# 156-01A_LCNC_Combo_board.net
KiCad netlist of a schematic drawn in EAGLE
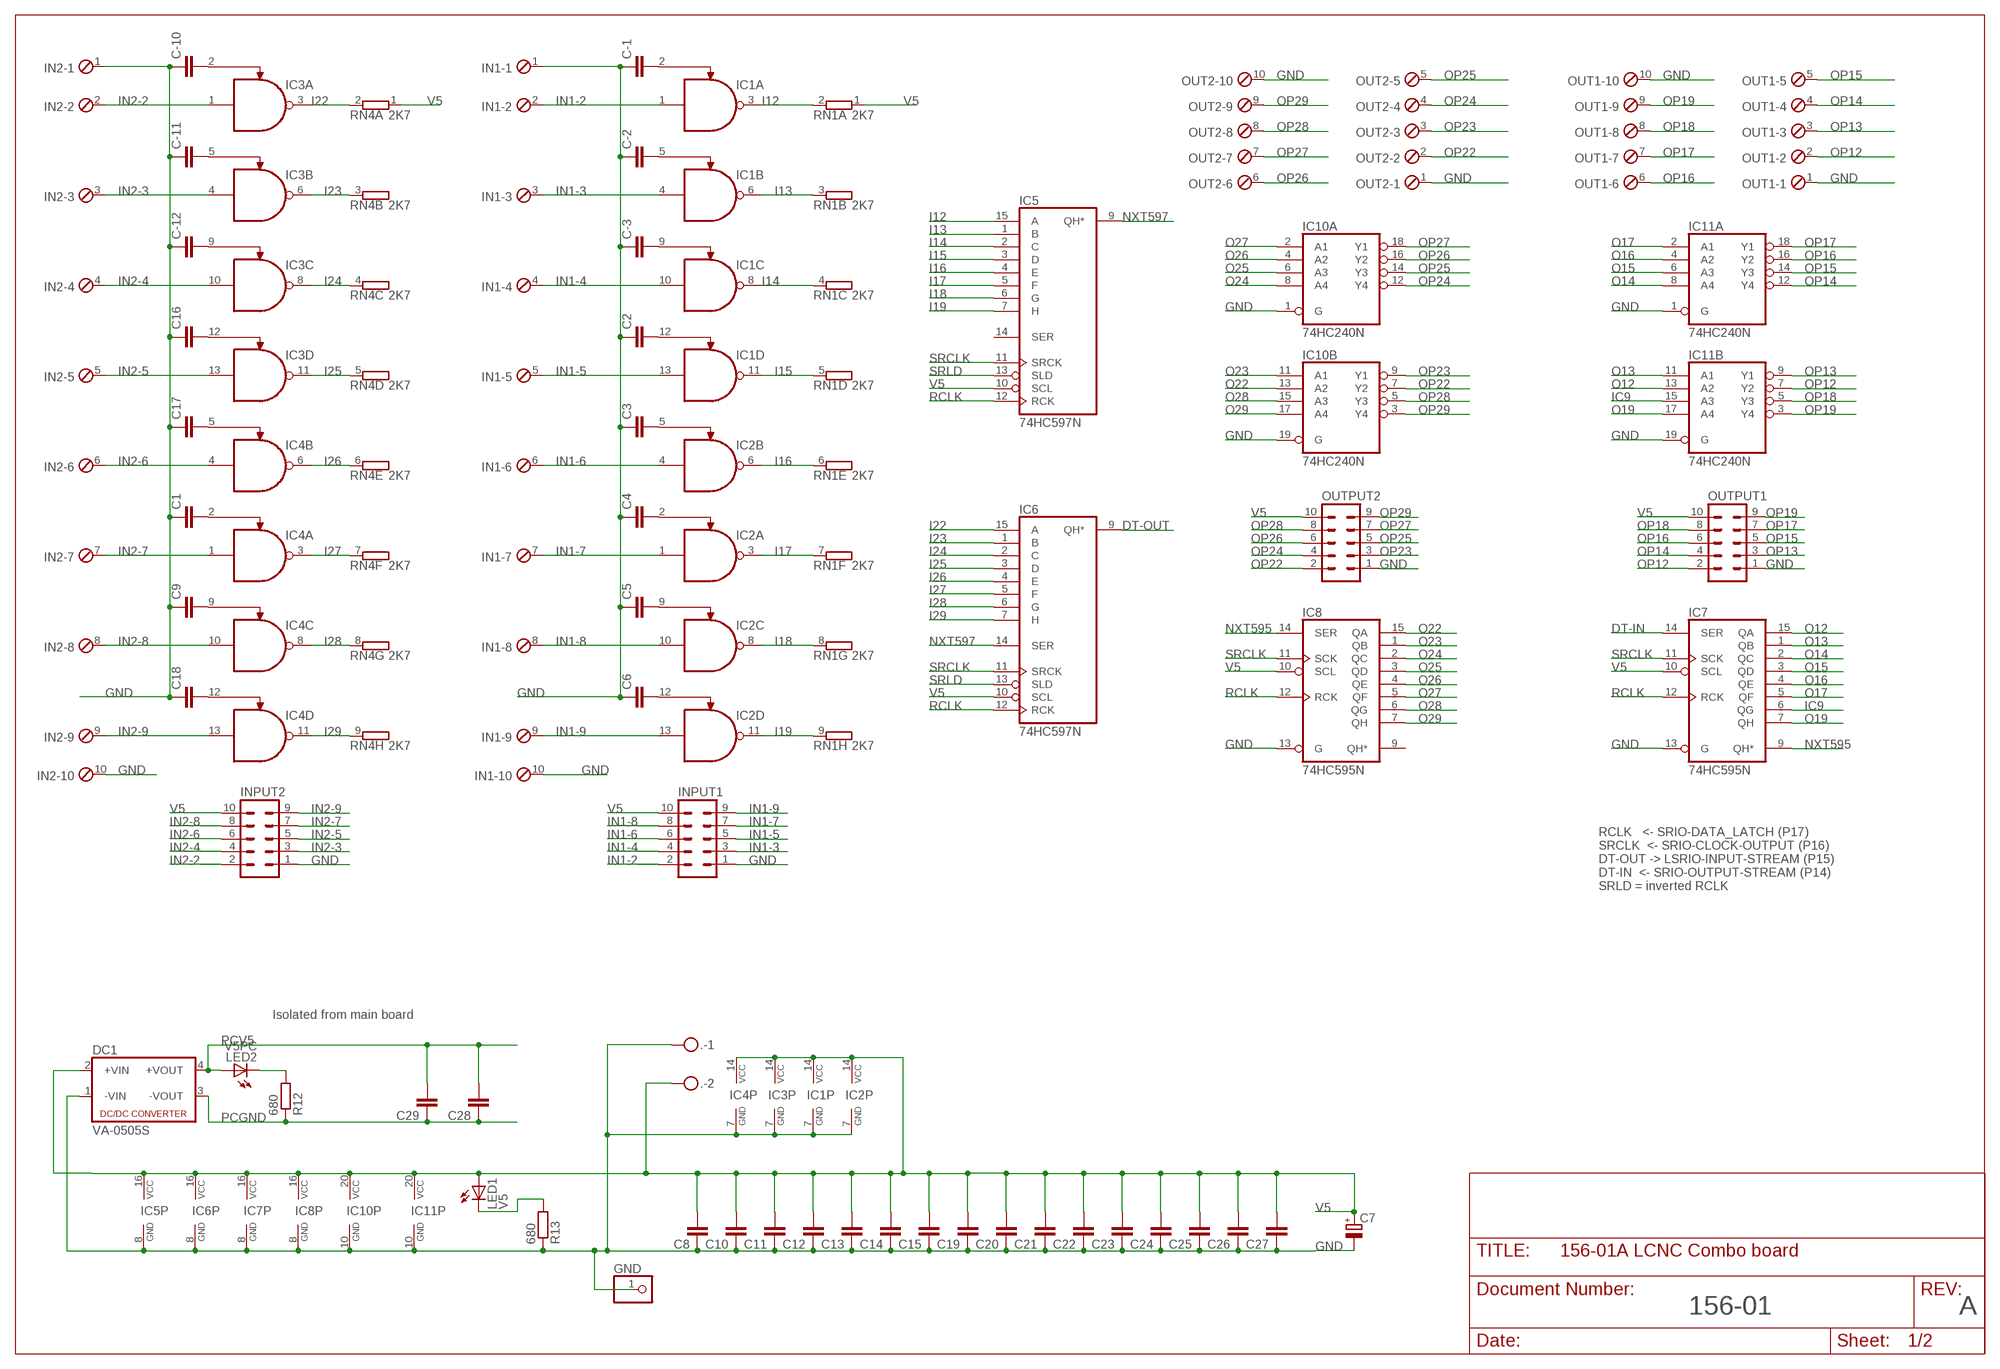
[diagram p0: schematic, sheet 1]
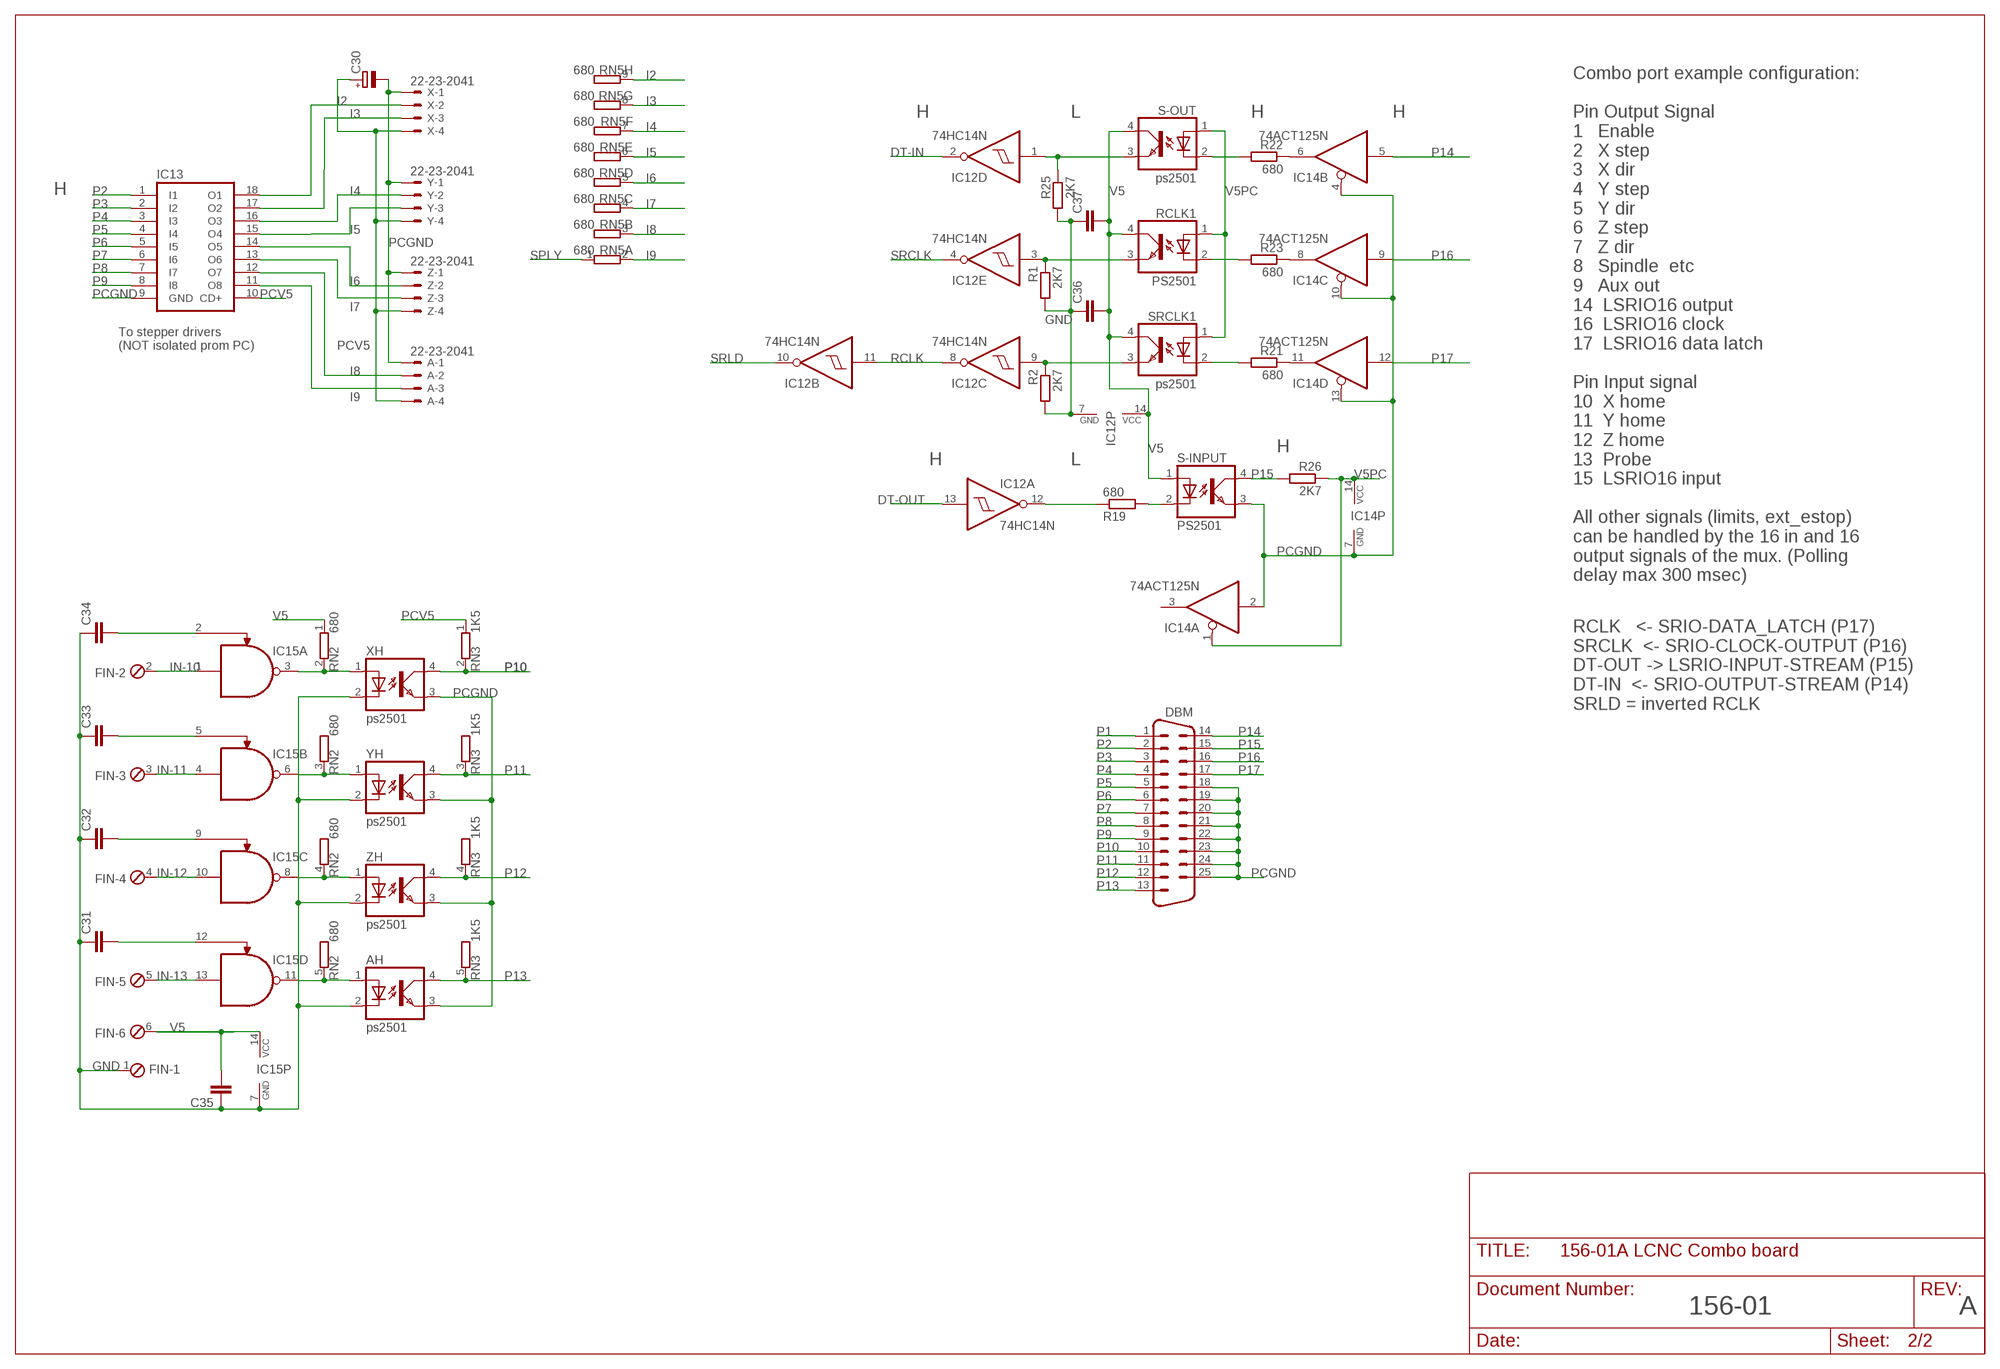
[diagram p1: schematic, sheet 2]

(export (version "E")
  (design (tool "Eeschema 10.0.6"))
  (components
    (comp (ref ".")
      (value "MKDSN1,5/2-5,08")
      (footprint "eagle-import:MKDSN1,5_2-5,08")
      (libsource (lib "eagle-import") (part "MKDSN1,5/2-5,08"))
    )
    (comp (ref "C-1")
      (value "C-EU025-024X044")
      (footprint "eagle-import:C025-024X044")
      (libsource (lib "eagle-import") (part "C-EU025-024X044"))
    )
    (comp (ref "C-2")
      (value "C-EU025-024X044")
      (footprint "eagle-import:C025-024X044")
      (libsource (lib "eagle-import") (part "C-EU025-024X044"))
    )
    (comp (ref "C-3")
      (value "C-EU025-024X044")
      (footprint "eagle-import:C025-024X044")
      (libsource (lib "eagle-import") (part "C-EU025-024X044"))
    )
    (comp (ref "C-10")
      (value "C-EU025-024X044")
      (footprint "eagle-import:C025-024X044")
      (libsource (lib "eagle-import") (part "C-EU025-024X044"))
    )
    (comp (ref "C-11")
      (value "C-EU025-024X044")
      (footprint "eagle-import:C025-024X044")
      (libsource (lib "eagle-import") (part "C-EU025-024X044"))
    )
    (comp (ref "C-12")
      (value "C-EU025-024X044")
      (footprint "eagle-import:C025-024X044")
      (libsource (lib "eagle-import") (part "C-EU025-024X044"))
    )
    (comp (ref "C1")
      (value "C-EU025-024X044")
      (footprint "eagle-import:C025-024X044")
      (libsource (lib "eagle-import") (part "C-EU025-024X044"))
    )
    (comp (ref "C2")
      (value "C-EU025-024X044")
      (footprint "eagle-import:C025-024X044")
      (libsource (lib "eagle-import") (part "C-EU025-024X044"))
    )
    (comp (ref "C3")
      (value "C-EU025-024X044")
      (footprint "eagle-import:C025-024X044")
      (libsource (lib "eagle-import") (part "C-EU025-024X044"))
    )
    (comp (ref "C4")
      (value "C-EU025-024X044")
      (footprint "eagle-import:C025-024X044")
      (libsource (lib "eagle-import") (part "C-EU025-024X044"))
    )
    (comp (ref "C5")
      (value "C-EU025-024X044")
      (footprint "eagle-import:C025-024X044")
      (libsource (lib "eagle-import") (part "C-EU025-024X044"))
    )
    (comp (ref "C6")
      (value "C-EU025-024X044")
      (footprint "eagle-import:C025-024X044")
      (libsource (lib "eagle-import") (part "C-EU025-024X044"))
    )
    (comp (ref "C7")
      (value "CPOL-EUE3.5-8")
      (footprint "eagle-import:E3,5-8")
      (libsource (lib "eagle-import") (part "CPOL-EUE3.5-8"))
    )
    (comp (ref "C8")
      (value "C-EU025-024X044")
      (footprint "eagle-import:C025-024X044")
      (libsource (lib "eagle-import") (part "C-EU025-024X044"))
    )
    (comp (ref "C9")
      (value "C-EU025-024X044")
      (footprint "eagle-import:C025-024X044")
      (libsource (lib "eagle-import") (part "C-EU025-024X044"))
    )
    (comp (ref "C10")
      (value "C-EU025-024X044")
      (footprint "eagle-import:C025-024X044")
      (libsource (lib "eagle-import") (part "C-EU025-024X044"))
    )
    (comp (ref "C11")
      (value "C-EU025-024X044")
      (footprint "eagle-import:C025-024X044")
      (libsource (lib "eagle-import") (part "C-EU025-024X044"))
    )
    (comp (ref "C12")
      (value "C-EU025-024X044")
      (footprint "eagle-import:C025-024X044")
      (libsource (lib "eagle-import") (part "C-EU025-024X044"))
    )
    (comp (ref "C13")
      (value "C-EU025-024X044")
      (footprint "eagle-import:C025-024X044")
      (libsource (lib "eagle-import") (part "C-EU025-024X044"))
    )
    (comp (ref "C14")
      (value "C-EU025-024X044")
      (footprint "eagle-import:C025-024X044")
      (libsource (lib "eagle-import") (part "C-EU025-024X044"))
    )
    (comp (ref "C15")
      (value "C-EU025-024X044")
      (footprint "eagle-import:C025-024X044")
      (libsource (lib "eagle-import") (part "C-EU025-024X044"))
    )
    (comp (ref "C16")
      (value "C-EU025-024X044")
      (footprint "eagle-import:C025-024X044")
      (libsource (lib "eagle-import") (part "C-EU025-024X044"))
    )
    (comp (ref "C17")
      (value "C-EU025-024X044")
      (footprint "eagle-import:C025-024X044")
      (libsource (lib "eagle-import") (part "C-EU025-024X044"))
    )
    (comp (ref "C18")
      (value "C-EU025-024X044")
      (footprint "eagle-import:C025-024X044")
      (libsource (lib "eagle-import") (part "C-EU025-024X044"))
    )
    (comp (ref "C19")
      (value "C-EU025-024X044")
      (footprint "eagle-import:C025-024X044")
      (libsource (lib "eagle-import") (part "C-EU025-024X044"))
    )
    (comp (ref "C20")
      (value "C-EU025-024X044")
      (footprint "eagle-import:C025-024X044")
      (libsource (lib "eagle-import") (part "C-EU025-024X044"))
    )
    (comp (ref "C21")
      (value "C-EU025-024X044")
      (footprint "eagle-import:C025-024X044")
      (libsource (lib "eagle-import") (part "C-EU025-024X044"))
    )
    (comp (ref "C22")
      (value "C-EU025-024X044")
      (footprint "eagle-import:C025-024X044")
      (libsource (lib "eagle-import") (part "C-EU025-024X044"))
    )
    (comp (ref "C23")
      (value "C-EU025-024X044")
      (footprint "eagle-import:C025-024X044")
      (libsource (lib "eagle-import") (part "C-EU025-024X044"))
    )
    (comp (ref "C24")
      (value "C-EU025-024X044")
      (footprint "eagle-import:C025-024X044")
      (libsource (lib "eagle-import") (part "C-EU025-024X044"))
    )
    (comp (ref "C25")
      (value "C-EU025-024X044")
      (footprint "eagle-import:C025-024X044")
      (libsource (lib "eagle-import") (part "C-EU025-024X044"))
    )
    (comp (ref "C26")
      (value "C-EU025-024X044")
      (footprint "eagle-import:C025-024X044")
      (libsource (lib "eagle-import") (part "C-EU025-024X044"))
    )
    (comp (ref "C27")
      (value "C-EU025-024X044")
      (footprint "eagle-import:C025-024X044")
      (libsource (lib "eagle-import") (part "C-EU025-024X044"))
    )
    (comp (ref "C28")
      (value "C-EU025-024X044")
      (footprint "eagle-import:C025-024X044")
      (libsource (lib "eagle-import") (part "C-EU025-024X044"))
    )
    (comp (ref "C29")
      (value "C-EU025-024X044")
      (footprint "eagle-import:C025-024X044")
      (libsource (lib "eagle-import") (part "C-EU025-024X044"))
    )
    (comp (ref "DC1")
      (value "VA-0505S")
      (footprint "eagle-import:4SIL")
      (libsource (lib "eagle-import") (part "VA-?S0505"))
    )
    (comp (ref "GND")
      (value "PINHD-1X1")
      (footprint "eagle-import:1X01")
      (libsource (lib "eagle-import") (part "PINHD-1X1"))
    )
    (comp (ref "IC1")
      (value "MC1489DIP")
      (footprint "eagle-import:DIL14")
      (libsource (lib "eagle-import") (part "MC1489DIP"))
    )
    (comp (ref "IC2")
      (value "MC1489DIP")
      (footprint "eagle-import:DIL14")
      (libsource (lib "eagle-import") (part "MC1489DIP"))
    )
    (comp (ref "IC3")
      (value "MC1489DIP")
      (footprint "eagle-import:DIL14")
      (libsource (lib "eagle-import") (part "MC1489DIP"))
    )
    (comp (ref "IC4")
      (value "MC1489DIP")
      (footprint "eagle-import:DIL14")
      (libsource (lib "eagle-import") (part "MC1489DIP"))
    )
    (comp (ref "IC5")
      (value "74HC597N")
      (footprint "eagle-import:DIL16")
      (libsource (lib "eagle-import") (part "74597NHC"))
    )
    (comp (ref "IC6")
      (value "74HC597N")
      (footprint "eagle-import:DIL16")
      (libsource (lib "eagle-import") (part "74597NHC"))
    )
    (comp (ref "IC7")
      (value "74HC595N")
      (footprint "eagle-import:DIL16")
      (libsource (lib "eagle-import") (part "74595NHC"))
    )
    (comp (ref "IC8")
      (value "74HC595N")
      (footprint "eagle-import:DIL16")
      (libsource (lib "eagle-import") (part "74595NHC"))
    )
    (comp (ref "IC10")
      (value "74HC240N")
      (footprint "eagle-import:DIL20")
      (libsource (lib "eagle-import") (part "74240NHC"))
    )
    (comp (ref "IC11")
      (value "74HC240N")
      (footprint "eagle-import:DIL20")
      (libsource (lib "eagle-import") (part "74240NHC"))
    )
    (comp (ref "IN1")
      (value "MPT10")
      (footprint "eagle-import:10POL254")
      (libsource (lib "eagle-import") (part "MPT10"))
    )
    (comp (ref "IN2")
      (value "MPT10")
      (footprint "eagle-import:10POL254")
      (libsource (lib "eagle-import") (part "MPT10"))
    )
    (comp (ref "INPUT1")
      (value "ML10")
      (footprint "eagle-import:ML10")
      (libsource (lib "eagle-import") (part "ML10"))
    )
    (comp (ref "INPUT2")
      (value "ML10")
      (footprint "eagle-import:ML10")
      (libsource (lib "eagle-import") (part "ML10"))
    )
    (comp (ref "LED1")
      (value "V5")
      (footprint "eagle-import:LED3MM")
      (libsource (lib "eagle-import") (part "LED3MM"))
    )
    (comp (ref "LED2")
      (value "V5PC")
      (footprint "eagle-import:LED3MM")
      (libsource (lib "eagle-import") (part "LED3MM"))
    )
    (comp (ref "OUT1")
      (value "MPT10")
      (footprint "eagle-import:10POL254")
      (libsource (lib "eagle-import") (part "MPT10"))
    )
    (comp (ref "OUT2")
      (value "MPT10")
      (footprint "eagle-import:10POL254")
      (libsource (lib "eagle-import") (part "MPT10"))
    )
    (comp (ref "OUTPUT1")
      (value "ML10")
      (footprint "eagle-import:ML10")
      (libsource (lib "eagle-import") (part "ML10"))
    )
    (comp (ref "OUTPUT2")
      (value "ML10")
      (footprint "eagle-import:ML10")
      (libsource (lib "eagle-import") (part "ML10"))
    )
    (comp (ref "R12")
      (value "680")
      (footprint "eagle-import:0207_10")
      (libsource (lib "eagle-import") (part "R-EU_0207/10"))
    )
    (comp (ref "R13")
      (value "680")
      (footprint "eagle-import:0207_10")
      (libsource (lib "eagle-import") (part "R-EU_0207/10"))
    )
    (comp (ref "RN1")
      (value "2K7")
      (footprint "eagle-import:SIL9")
      (libsource (lib "eagle-import") (part "GE08R"))
    )
    (comp (ref "RN4")
      (value "2K7")
      (footprint "eagle-import:SIL9")
      (libsource (lib "eagle-import") (part "GE08R"))
    )
    (comp (ref "A")
      (value "22-23-2041")
      (footprint "eagle-import:22-23-2041")
      (fields (field (name "MF") "MOLEX"))
      (libsource (lib "eagle-import") (part "22-23-2041"))
    )
    (comp (ref "AH")
      (value "ps2501")
      (footprint "eagle-import:DIL04")
      (fields (field (name "MPN") "PC817X4J000F"))
      (libsource (lib "eagle-import") (part "PC817"))
    )
    (comp (ref "C30")
      (value "CPOL-EUE2.5-6")
      (footprint "eagle-import:E2,5-6")
      (libsource (lib "eagle-import") (part "CPOL-EUE2.5-6"))
    )
    (comp (ref "C31")
      (value "C-EU025-024X044")
      (footprint "eagle-import:C025-024X044")
      (libsource (lib "eagle-import") (part "C-EU025-024X044"))
    )
    (comp (ref "C32")
      (value "C-EU025-024X044")
      (footprint "eagle-import:C025-024X044")
      (libsource (lib "eagle-import") (part "C-EU025-024X044"))
    )
    (comp (ref "C33")
      (value "C-EU025-024X044")
      (footprint "eagle-import:C025-024X044")
      (libsource (lib "eagle-import") (part "C-EU025-024X044"))
    )
    (comp (ref "C34")
      (value "C-EU025-024X044")
      (footprint "eagle-import:C025-024X044")
      (libsource (lib "eagle-import") (part "C-EU025-024X044"))
    )
    (comp (ref "C35")
      (value "C-EU025-024X044")
      (footprint "eagle-import:C025-024X044")
      (libsource (lib "eagle-import") (part "C-EU025-024X044"))
    )
    (comp (ref "C36")
      (value "C-EU025-024X044")
      (footprint "eagle-import:C025-024X044")
      (libsource (lib "eagle-import") (part "C-EU025-024X044"))
    )
    (comp (ref "C37")
      (value "C-EU025-024X044")
      (footprint "eagle-import:C025-024X044")
      (libsource (lib "eagle-import") (part "C-EU025-024X044"))
    )
    (comp (ref "DBM")
      (value "M25HP")
      (footprint "eagle-import:M25HP")
      (libsource (lib "eagle-import") (part "M25HP"))
    )
    (comp (ref "FIN")
      (value "MPT6")
      (footprint "eagle-import:6POL254")
      (libsource (lib "eagle-import") (part "MPT6"))
    )
    (comp (ref "IC12")
      (value "74HC14N")
      (footprint "eagle-import:DIL14")
      (libsource (lib "eagle-import") (part "7414NHC"))
    )
    (comp (ref "IC13")
      (value "ULN2803A")
      (footprint "eagle-import:DIL18")
      (libsource (lib "eagle-import") (part "ULN2803A"))
    )
    (comp (ref "IC14")
      (value "74ACT125N")
      (footprint "eagle-import:DIL14")
      (libsource (lib "eagle-import") (part "74125NACT"))
    )
    (comp (ref "IC15")
      (value "MC1489DIP")
      (footprint "eagle-import:DIL14")
      (libsource (lib "eagle-import") (part "my-components_MC1489DIP"))
    )
    (comp (ref "R1")
      (value "2K7")
      (footprint "eagle-import:0207_10")
      (libsource (lib "eagle-import") (part "R-EU_0207/10"))
    )
    (comp (ref "R2")
      (value "2K7")
      (footprint "eagle-import:0207_10")
      (libsource (lib "eagle-import") (part "R-EU_0207/10"))
    )
    (comp (ref "R19")
      (value "680")
      (footprint "eagle-import:0207_10")
      (libsource (lib "eagle-import") (part "R-EU_0207/10"))
    )
    (comp (ref "R21")
      (value "680")
      (footprint "eagle-import:0207_10")
      (libsource (lib "eagle-import") (part "R-EU_0207/10"))
    )
    (comp (ref "R22")
      (value "680")
      (footprint "eagle-import:0207_10")
      (libsource (lib "eagle-import") (part "R-EU_0207/10"))
    )
    (comp (ref "R23")
      (value "680")
      (footprint "eagle-import:0207_10")
      (libsource (lib "eagle-import") (part "R-EU_0207/10"))
    )
    (comp (ref "R25")
      (value "2K7")
      (footprint "eagle-import:0207_10")
      (libsource (lib "eagle-import") (part "R-EU_0207/10"))
    )
    (comp (ref "R26")
      (value "2K7")
      (footprint "eagle-import:0207_10")
      (libsource (lib "eagle-import") (part "R-EU_0207/10"))
    )
    (comp (ref "RCLK1")
      (value "PS2501")
      (footprint "eagle-import:DIL04")
      (fields (field (name "MPN") "PC817X4J000F"))
      (libsource (lib "eagle-import") (part "PC817"))
    )
    (comp (ref "RN2")
      (value "680")
      (footprint "eagle-import:SIL5")
      (libsource (lib "eagle-import") (part "GE04RP"))
    )
    (comp (ref "RN3")
      (value "1K5")
      (footprint "eagle-import:SIL5")
      (libsource (lib "eagle-import") (part "GE04RP"))
    )
    (comp (ref "RN5")
      (value "680")
      (footprint "eagle-import:SIL9")
      (libsource (lib "eagle-import") (part "GE08R"))
    )
    (comp (ref "S-INPUT")
      (value "PS2501")
      (footprint "eagle-import:DIL04")
      (fields (field (name "MPN") "PC817X4J000F"))
      (libsource (lib "eagle-import") (part "PC817"))
    )
    (comp (ref "S-OUT")
      (value "ps2501")
      (footprint "eagle-import:DIL04")
      (fields (field (name "MPN") "PC817X4J000F"))
      (libsource (lib "eagle-import") (part "PC817"))
    )
    (comp (ref "SRCLK1")
      (value "ps2501")
      (footprint "eagle-import:DIL04")
      (fields (field (name "MPN") "PC817X4J000F"))
      (libsource (lib "eagle-import") (part "PC817"))
    )
    (comp (ref "X")
      (value "22-23-2041")
      (footprint "eagle-import:22-23-2041")
      (fields (field (name "MF") "MOLEX"))
      (libsource (lib "eagle-import") (part "22-23-2041"))
    )
    (comp (ref "XH")
      (value "ps2501")
      (footprint "eagle-import:DIL04")
      (fields (field (name "MPN") "PC817X4J000F"))
      (libsource (lib "eagle-import") (part "PC817"))
    )
    (comp (ref "Y")
      (value "22-23-2041")
      (footprint "eagle-import:22-23-2041")
      (fields (field (name "MF") "MOLEX"))
      (libsource (lib "eagle-import") (part "22-23-2041"))
    )
    (comp (ref "YH")
      (value "ps2501")
      (footprint "eagle-import:DIL04")
      (fields (field (name "MPN") "PC817X4J000F"))
      (libsource (lib "eagle-import") (part "PC817"))
    )
    (comp (ref "Z")
      (value "22-23-2041")
      (footprint "eagle-import:22-23-2041")
      (fields (field (name "MF") "MOLEX"))
      (libsource (lib "eagle-import") (part "22-23-2041"))
    )
    (comp (ref "ZH")
      (value "ps2501")
      (footprint "eagle-import:DIL04")
      (fields (field (name "MPN") "PC817X4J000F"))
      (libsource (lib "eagle-import") (part "PC817"))
    )
  )
  (nets
    (net (code "1") (name "DT-IN") (class "Default")
      (node (ref "IC12") (pin "2") (pinfunction "O_2") (pintype "output"))
      (node (ref "IC7") (pin "14") (pinfunction "SER_14") (pintype "input"))
    )
    (net (code "2") (name "DT-OUT") (class "Default")
      (node (ref "IC12") (pin "13") (pinfunction "I_13") (pintype "input"))
      (node (ref "IC6") (pin "9") (pinfunction "QH*_9") (pintype "output"))
    )
    (net (code "3") (name "GND") (class "Default")
      (node (ref ".") (pin "1") (pinfunction "KL_1") (pintype "passive"))
      (node (ref "AH") (pin "2") (pinfunction "C_2") (pintype "passive"))
      (node (ref "C-1") (pin "1") (pinfunction "1_1") (pintype "passive"))
      (node (ref "C-10") (pin "1") (pinfunction "1_1") (pintype "passive"))
      (node (ref "C-11") (pin "1") (pinfunction "1_1") (pintype "passive"))
      (node (ref "C-12") (pin "1") (pinfunction "1_1") (pintype "passive"))
      (node (ref "C-2") (pin "1") (pinfunction "1_1") (pintype "passive"))
      (node (ref "C-3") (pin "1") (pinfunction "1_1") (pintype "passive"))
      (node (ref "C1") (pin "1") (pinfunction "1_1") (pintype "passive"))
      (node (ref "C10") (pin "1") (pinfunction "1_1") (pintype "passive"))
      (node (ref "C11") (pin "1") (pinfunction "1_1") (pintype "passive"))
      (node (ref "C12") (pin "1") (pinfunction "1_1") (pintype "passive"))
      (node (ref "C13") (pin "1") (pinfunction "1_1") (pintype "passive"))
      (node (ref "C14") (pin "1") (pinfunction "1_1") (pintype "passive"))
      (node (ref "C15") (pin "1") (pinfunction "1_1") (pintype "passive"))
      (node (ref "C16") (pin "1") (pinfunction "1_1") (pintype "passive"))
      (node (ref "C17") (pin "1") (pinfunction "1_1") (pintype "passive"))
      (node (ref "C18") (pin "1") (pinfunction "1_1") (pintype "passive"))
      (node (ref "C19") (pin "1") (pinfunction "1_1") (pintype "passive"))
      (node (ref "C2") (pin "1") (pinfunction "1_1") (pintype "passive"))
      (node (ref "C20") (pin "1") (pinfunction "1_1") (pintype "passive"))
      (node (ref "C21") (pin "1") (pinfunction "1_1") (pintype "passive"))
      (node (ref "C22") (pin "1") (pinfunction "1_1") (pintype "passive"))
      (node (ref "C23") (pin "1") (pinfunction "1_1") (pintype "passive"))
      (node (ref "C24") (pin "1") (pinfunction "1_1") (pintype "passive"))
      (node (ref "C25") (pin "1") (pinfunction "1_1") (pintype "passive"))
      (node (ref "C26") (pin "1") (pinfunction "1_1") (pintype "passive"))
      (node (ref "C27") (pin "1") (pinfunction "1_1") (pintype "passive"))
      (node (ref "C3") (pin "1") (pinfunction "1_1") (pintype "passive"))
      (node (ref "C31") (pin "1") (pinfunction "1_1") (pintype "passive"))
      (node (ref "C32") (pin "1") (pinfunction "1_1") (pintype "passive"))
      (node (ref "C33") (pin "1") (pinfunction "1_1") (pintype "passive"))
      (node (ref "C34") (pin "1") (pinfunction "1_1") (pintype "passive"))
      (node (ref "C35") (pin "1") (pinfunction "1_1") (pintype "passive"))
      (node (ref "C36") (pin "1") (pinfunction "1_1") (pintype "passive"))
      (node (ref "C37") (pin "1") (pinfunction "1_1") (pintype "passive"))
      (node (ref "C4") (pin "1") (pinfunction "1_1") (pintype "passive"))
      (node (ref "C5") (pin "1") (pinfunction "1_1") (pintype "passive"))
      (node (ref "C6") (pin "1") (pinfunction "1_1") (pintype "passive"))
      (node (ref "C7") (pin "-") (pinfunction "-_-") (pintype "passive"))
      (node (ref "C8") (pin "1") (pinfunction "1_1") (pintype "passive"))
      (node (ref "C9") (pin "1") (pinfunction "1_1") (pintype "passive"))
      (node (ref "DC1") (pin "1") (pinfunction "-VIN_1") (pintype "passive"))
      (node (ref "FIN") (pin "1") (pinfunction "1_1") (pintype "passive"))
      (node (ref "GND") (pin "1") (pinfunction "1_1") (pintype "passive"))
      (node (ref "IC1") (pin "7") (pinfunction "GND_7") (pintype "power_in"))
      (node (ref "IC10") (pin "1") (pinfunction "G_1") (pintype "input"))
      (node (ref "IC10") (pin "10") (pinfunction "GND_10") (pintype "power_in"))
      (node (ref "IC10") (pin "19") (pinfunction "G_19") (pintype "input"))
      (node (ref "IC11") (pin "1") (pinfunction "G_1") (pintype "input"))
      (node (ref "IC11") (pin "10") (pinfunction "GND_10") (pintype "power_in"))
      (node (ref "IC11") (pin "19") (pinfunction "G_19") (pintype "input"))
      (node (ref "IC12") (pin "7") (pinfunction "GND_7") (pintype "power_in"))
      (node (ref "IC15") (pin "7") (pinfunction "GND_7") (pintype "power_in"))
      (node (ref "IC2") (pin "7") (pinfunction "GND_7") (pintype "power_in"))
      (node (ref "IC3") (pin "7") (pinfunction "GND_7") (pintype "power_in"))
      (node (ref "IC4") (pin "7") (pinfunction "GND_7") (pintype "power_in"))
      (node (ref "IC5") (pin "8") (pinfunction "GND_8") (pintype "power_in"))
      (node (ref "IC6") (pin "8") (pinfunction "GND_8") (pintype "power_in"))
      (node (ref "IC7") (pin "13") (pinfunction "G_13") (pintype "input"))
      (node (ref "IC7") (pin "8") (pinfunction "GND_8") (pintype "power_in"))
      (node (ref "IC8") (pin "13") (pinfunction "G_13") (pintype "input"))
      (node (ref "IC8") (pin "8") (pinfunction "GND_8") (pintype "power_in"))
      (node (ref "IN1") (pin "1") (pinfunction "1_1") (pintype "passive"))
      (node (ref "IN1") (pin "10") (pinfunction "1_10") (pintype "passive"))
      (node (ref "IN2") (pin "1") (pinfunction "1_1") (pintype "passive"))
      (node (ref "IN2") (pin "10") (pinfunction "1_10") (pintype "passive"))
      (node (ref "INPUT1") (pin "1") (pinfunction "1_1") (pintype "passive"))
      (node (ref "INPUT2") (pin "1") (pinfunction "1_1") (pintype "passive"))
      (node (ref "OUT1") (pin "1") (pinfunction "1_1") (pintype "passive"))
      (node (ref "OUT1") (pin "10") (pinfunction "1_10") (pintype "passive"))
      (node (ref "OUT2") (pin "1") (pinfunction "1_1") (pintype "passive"))
      (node (ref "OUT2") (pin "10") (pinfunction "1_10") (pintype "passive"))
      (node (ref "OUTPUT1") (pin "1") (pinfunction "1_1") (pintype "passive"))
      (node (ref "OUTPUT2") (pin "1") (pinfunction "1_1") (pintype "passive"))
      (node (ref "R1") (pin "2") (pinfunction "2_2") (pintype "passive"))
      (node (ref "R13") (pin "1") (pinfunction "1_1") (pintype "passive"))
      (node (ref "R2") (pin "2") (pinfunction "2_2") (pintype "passive"))
      (node (ref "R25") (pin "2") (pinfunction "2_2") (pintype "passive"))
      (node (ref "XH") (pin "2") (pinfunction "C_2") (pintype "passive"))
      (node (ref "YH") (pin "2") (pinfunction "C_2") (pintype "passive"))
      (node (ref "ZH") (pin "2") (pinfunction "C_2") (pintype "passive"))
    )
    (net (code "4") (name "I2") (class "Default")
      (node (ref "IC13") (pin "18") (pinfunction "O1_18") (pintype "open_collector"))
      (node (ref "RN5") (pin "9") (pinfunction "2_9") (pintype "passive"))
      (node (ref "X") (pin "2") (pinfunction "S_2") (pintype "passive"))
    )
    (net (code "5") (name "I3") (class "Default")
      (node (ref "IC13") (pin "17") (pinfunction "O2_17") (pintype "open_collector"))
      (node (ref "RN5") (pin "8") (pinfunction "2_8") (pintype "passive"))
      (node (ref "X") (pin "3") (pinfunction "S_3") (pintype "passive"))
    )
    (net (code "6") (name "I4") (class "Default")
      (node (ref "IC13") (pin "16") (pinfunction "O3_16") (pintype "open_collector"))
      (node (ref "RN5") (pin "7") (pinfunction "2_7") (pintype "passive"))
      (node (ref "Y") (pin "2") (pinfunction "S_2") (pintype "passive"))
    )
    (net (code "7") (name "I5") (class "Default")
      (node (ref "IC13") (pin "15") (pinfunction "O4_15") (pintype "open_collector"))
      (node (ref "RN5") (pin "6") (pinfunction "2_6") (pintype "passive"))
      (node (ref "Y") (pin "3") (pinfunction "S_3") (pintype "passive"))
    )
    (net (code "8") (name "I6") (class "Default")
      (node (ref "IC13") (pin "14") (pinfunction "O5_14") (pintype "open_collector"))
      (node (ref "RN5") (pin "5") (pinfunction "2_5") (pintype "passive"))
      (node (ref "Z") (pin "2") (pinfunction "S_2") (pintype "passive"))
    )
    (net (code "9") (name "I7") (class "Default")
      (node (ref "IC13") (pin "13") (pinfunction "O6_13") (pintype "open_collector"))
      (node (ref "RN5") (pin "4") (pinfunction "2_4") (pintype "passive"))
      (node (ref "Z") (pin "3") (pinfunction "S_3") (pintype "passive"))
    )
    (net (code "10") (name "I8") (class "Default")
      (node (ref "A") (pin "2") (pinfunction "S_2") (pintype "passive"))
      (node (ref "IC13") (pin "12") (pinfunction "O7_12") (pintype "open_collector"))
      (node (ref "RN5") (pin "3") (pinfunction "2_3") (pintype "passive"))
    )
    (net (code "11") (name "I9") (class "Default")
      (node (ref "A") (pin "3") (pinfunction "S_3") (pintype "passive"))
      (node (ref "IC13") (pin "11") (pinfunction "O8_11") (pintype "open_collector"))
      (node (ref "RN5") (pin "2") (pinfunction "2_2") (pintype "passive"))
    )
    (net (code "12") (name "I12") (class "Default")
      (node (ref "IC1") (pin "3") (pinfunction "O_3") (pintype "output"))
      (node (ref "IC5") (pin "15") (pinfunction "A_15") (pintype "input"))
      (node (ref "RN1") (pin "2") (pinfunction "2_2") (pintype "passive"))
    )
    (net (code "13") (name "I13") (class "Default")
      (node (ref "IC1") (pin "6") (pinfunction "O_6") (pintype "output"))
      (node (ref "IC5") (pin "1") (pinfunction "B_1") (pintype "input"))
      (node (ref "RN1") (pin "3") (pinfunction "2_3") (pintype "passive"))
    )
    (net (code "14") (name "I14") (class "Default")
      (node (ref "IC1") (pin "8") (pinfunction "O_8") (pintype "output"))
      (node (ref "IC5") (pin "2") (pinfunction "C_2") (pintype "input"))
      (node (ref "RN1") (pin "4") (pinfunction "2_4") (pintype "passive"))
    )
    (net (code "15") (name "I15") (class "Default")
      (node (ref "IC1") (pin "11") (pinfunction "O_11") (pintype "output"))
      (node (ref "IC5") (pin "3") (pinfunction "D_3") (pintype "input"))
      (node (ref "RN1") (pin "5") (pinfunction "2_5") (pintype "passive"))
    )
    (net (code "16") (name "I16") (class "Default")
      (node (ref "IC2") (pin "6") (pinfunction "O_6") (pintype "output"))
      (node (ref "IC5") (pin "4") (pinfunction "E_4") (pintype "input"))
      (node (ref "RN1") (pin "6") (pinfunction "2_6") (pintype "passive"))
    )
    (net (code "17") (name "I17") (class "Default")
      (node (ref "IC2") (pin "3") (pinfunction "O_3") (pintype "output"))
      (node (ref "IC5") (pin "5") (pinfunction "F_5") (pintype "input"))
      (node (ref "RN1") (pin "7") (pinfunction "2_7") (pintype "passive"))
    )
    (net (code "18") (name "I18") (class "Default")
      (node (ref "IC2") (pin "8") (pinfunction "O_8") (pintype "output"))
      (node (ref "IC5") (pin "6") (pinfunction "G_6") (pintype "input"))
      (node (ref "RN1") (pin "8") (pinfunction "2_8") (pintype "passive"))
    )
    (net (code "19") (name "I19") (class "Default")
      (node (ref "IC2") (pin "11") (pinfunction "O_11") (pintype "output"))
      (node (ref "IC5") (pin "7") (pinfunction "H_7") (pintype "input"))
      (node (ref "RN1") (pin "9") (pinfunction "2_9") (pintype "passive"))
    )
    (net (code "20") (name "I22") (class "Default")
      (node (ref "IC3") (pin "3") (pinfunction "O_3") (pintype "output"))
      (node (ref "IC6") (pin "15") (pinfunction "A_15") (pintype "input"))
      (node (ref "RN4") (pin "2") (pinfunction "2_2") (pintype "passive"))
    )
    (net (code "21") (name "I23") (class "Default")
      (node (ref "IC3") (pin "6") (pinfunction "O_6") (pintype "output"))
      (node (ref "IC6") (pin "1") (pinfunction "B_1") (pintype "input"))
      (node (ref "RN4") (pin "3") (pinfunction "2_3") (pintype "passive"))
    )
    (net (code "22") (name "I24") (class "Default")
      (node (ref "IC3") (pin "8") (pinfunction "O_8") (pintype "output"))
      (node (ref "IC6") (pin "2") (pinfunction "C_2") (pintype "input"))
      (node (ref "RN4") (pin "4") (pinfunction "2_4") (pintype "passive"))
    )
    (net (code "23") (name "I25") (class "Default")
      (node (ref "IC3") (pin "11") (pinfunction "O_11") (pintype "output"))
      (node (ref "IC6") (pin "3") (pinfunction "D_3") (pintype "input"))
      (node (ref "RN4") (pin "5") (pinfunction "2_5") (pintype "passive"))
    )
    (net (code "24") (name "I26") (class "Default")
      (node (ref "IC4") (pin "6") (pinfunction "O_6") (pintype "output"))
      (node (ref "IC6") (pin "4") (pinfunction "E_4") (pintype "input"))
      (node (ref "RN4") (pin "6") (pinfunction "2_6") (pintype "passive"))
    )
    (net (code "25") (name "I27") (class "Default")
      (node (ref "IC4") (pin "3") (pinfunction "O_3") (pintype "output"))
      (node (ref "IC6") (pin "5") (pinfunction "F_5") (pintype "input"))
      (node (ref "RN4") (pin "7") (pinfunction "2_7") (pintype "passive"))
    )
    (net (code "26") (name "I28") (class "Default")
      (node (ref "IC4") (pin "8") (pinfunction "O_8") (pintype "output"))
      (node (ref "IC6") (pin "6") (pinfunction "G_6") (pintype "input"))
      (node (ref "RN4") (pin "8") (pinfunction "2_8") (pintype "passive"))
    )
    (net (code "27") (name "I29") (class "Default")
      (node (ref "IC4") (pin "11") (pinfunction "O_11") (pintype "output"))
      (node (ref "IC6") (pin "7") (pinfunction "H_7") (pintype "input"))
      (node (ref "RN4") (pin "9") (pinfunction "2_9") (pintype "passive"))
    )
    (net (code "28") (name "IC9") (class "Default")
      (node (ref "IC11") (pin "15") (pinfunction "A3_15") (pintype "input"))
      (node (ref "IC7") (pin "6") (pinfunction "QG_6") (pintype "tri_state"))
    )
    (net (code "29") (name "IN-10") (class "Default")
      (node (ref "FIN") (pin "2") (pinfunction "1_2") (pintype "passive"))
      (node (ref "IC15") (pin "1") (pinfunction "I0_1") (pintype "input"))
    )
    (net (code "30") (name "IN-11") (class "Default")
      (node (ref "FIN") (pin "3") (pinfunction "1_3") (pintype "passive"))
      (node (ref "IC15") (pin "4") (pinfunction "I0_4") (pintype "input"))
    )
    (net (code "31") (name "IN-12") (class "Default")
      (node (ref "FIN") (pin "4") (pinfunction "1_4") (pintype "passive"))
      (node (ref "IC15") (pin "10") (pinfunction "I0_10") (pintype "input"))
    )
    (net (code "32") (name "IN-13") (class "Default")
      (node (ref "FIN") (pin "5") (pinfunction "1_5") (pintype "passive"))
      (node (ref "IC15") (pin "13") (pinfunction "I0_13") (pintype "input"))
    )
    (net (code "33") (name "IN1-2") (class "Default")
      (node (ref "IC1") (pin "1") (pinfunction "I0_1") (pintype "input"))
      (node (ref "IN1") (pin "2") (pinfunction "1_2") (pintype "passive"))
      (node (ref "INPUT1") (pin "2") (pinfunction "2_2") (pintype "passive"))
    )
    (net (code "34") (name "IN1-3") (class "Default")
      (node (ref "IC1") (pin "4") (pinfunction "I0_4") (pintype "input"))
      (node (ref "IN1") (pin "3") (pinfunction "1_3") (pintype "passive"))
      (node (ref "INPUT1") (pin "3") (pinfunction "3_3") (pintype "passive"))
    )
    (net (code "35") (name "IN1-4") (class "Default")
      (node (ref "IC1") (pin "10") (pinfunction "I0_10") (pintype "input"))
      (node (ref "IN1") (pin "4") (pinfunction "1_4") (pintype "passive"))
      (node (ref "INPUT1") (pin "4") (pinfunction "4_4") (pintype "passive"))
    )
    (net (code "36") (name "IN1-5") (class "Default")
      (node (ref "IC1") (pin "13") (pinfunction "I0_13") (pintype "input"))
      (node (ref "IN1") (pin "5") (pinfunction "1_5") (pintype "passive"))
      (node (ref "INPUT1") (pin "5") (pinfunction "5_5") (pintype "passive"))
    )
    (net (code "37") (name "IN1-6") (class "Default")
      (node (ref "IC2") (pin "4") (pinfunction "I0_4") (pintype "input"))
      (node (ref "IN1") (pin "6") (pinfunction "1_6") (pintype "passive"))
      (node (ref "INPUT1") (pin "6") (pinfunction "6_6") (pintype "passive"))
    )
    (net (code "38") (name "IN1-7") (class "Default")
      (node (ref "IC2") (pin "1") (pinfunction "I0_1") (pintype "input"))
      (node (ref "IN1") (pin "7") (pinfunction "1_7") (pintype "passive"))
      (node (ref "INPUT1") (pin "7") (pinfunction "7_7") (pintype "passive"))
    )
    (net (code "39") (name "IN1-8") (class "Default")
      (node (ref "IC2") (pin "10") (pinfunction "I0_10") (pintype "input"))
      (node (ref "IN1") (pin "8") (pinfunction "1_8") (pintype "passive"))
      (node (ref "INPUT1") (pin "8") (pinfunction "8_8") (pintype "passive"))
    )
    (net (code "40") (name "IN1-9") (class "Default")
      (node (ref "IC2") (pin "13") (pinfunction "I0_13") (pintype "input"))
      (node (ref "IN1") (pin "9") (pinfunction "1_9") (pintype "passive"))
      (node (ref "INPUT1") (pin "9") (pinfunction "9_9") (pintype "passive"))
    )
    (net (code "41") (name "IN2-2") (class "Default")
      (node (ref "IC3") (pin "1") (pinfunction "I0_1") (pintype "input"))
      (node (ref "IN2") (pin "2") (pinfunction "1_2") (pintype "passive"))
      (node (ref "INPUT2") (pin "2") (pinfunction "2_2") (pintype "passive"))
    )
    (net (code "42") (name "IN2-3") (class "Default")
      (node (ref "IC3") (pin "4") (pinfunction "I0_4") (pintype "input"))
      (node (ref "IN2") (pin "3") (pinfunction "1_3") (pintype "passive"))
      (node (ref "INPUT2") (pin "3") (pinfunction "3_3") (pintype "passive"))
    )
    (net (code "43") (name "IN2-4") (class "Default")
      (node (ref "IC3") (pin "10") (pinfunction "I0_10") (pintype "input"))
      (node (ref "IN2") (pin "4") (pinfunction "1_4") (pintype "passive"))
      (node (ref "INPUT2") (pin "4") (pinfunction "4_4") (pintype "passive"))
    )
    (net (code "44") (name "IN2-5") (class "Default")
      (node (ref "IC3") (pin "13") (pinfunction "I0_13") (pintype "input"))
      (node (ref "IN2") (pin "5") (pinfunction "1_5") (pintype "passive"))
      (node (ref "INPUT2") (pin "5") (pinfunction "5_5") (pintype "passive"))
    )
    (net (code "45") (name "IN2-6") (class "Default")
      (node (ref "IC4") (pin "4") (pinfunction "I0_4") (pintype "input"))
      (node (ref "IN2") (pin "6") (pinfunction "1_6") (pintype "passive"))
      (node (ref "INPUT2") (pin "6") (pinfunction "6_6") (pintype "passive"))
    )
    (net (code "46") (name "IN2-7") (class "Default")
      (node (ref "IC4") (pin "1") (pinfunction "I0_1") (pintype "input"))
      (node (ref "IN2") (pin "7") (pinfunction "1_7") (pintype "passive"))
      (node (ref "INPUT2") (pin "7") (pinfunction "7_7") (pintype "passive"))
    )
    (net (code "47") (name "IN2-8") (class "Default")
      (node (ref "IC4") (pin "10") (pinfunction "I0_10") (pintype "input"))
      (node (ref "IN2") (pin "8") (pinfunction "1_8") (pintype "passive"))
      (node (ref "INPUT2") (pin "8") (pinfunction "8_8") (pintype "passive"))
    )
    (net (code "48") (name "IN2-9") (class "Default")
      (node (ref "IC4") (pin "13") (pinfunction "I0_13") (pintype "input"))
      (node (ref "IN2") (pin "9") (pinfunction "1_9") (pintype "passive"))
      (node (ref "INPUT2") (pin "9") (pinfunction "9_9") (pintype "passive"))
    )
    (net (code "49") (name "NXT595") (class "Default")
      (node (ref "IC7") (pin "9") (pinfunction "QH*_9") (pintype "tri_state"))
      (node (ref "IC8") (pin "14") (pinfunction "SER_14") (pintype "input"))
    )
    (net (code "50") (name "NXT597") (class "Default")
      (node (ref "IC5") (pin "9") (pinfunction "QH*_9") (pintype "output"))
      (node (ref "IC6") (pin "14") (pinfunction "SER_14") (pintype "input"))
    )
    (net (code "51") (name "Net-(AH-A)") (class "Default")
      (node (ref "AH") (pin "1") (pinfunction "A_1") (pintype "passive"))
      (node (ref "IC15") (pin "11") (pinfunction "O_11") (pintype "output"))
      (node (ref "RN2") (pin "5") (pinfunction "2_5") (pintype "passive"))
    )
    (net (code "52") (name "Net-(IC1A-I1)") (class "Default")
      (node (ref "C-1") (pin "2") (pinfunction "2_2") (pintype "passive"))
      (node (ref "IC1") (pin "2") (pinfunction "I1_2") (pintype "input"))
    )
    (net (code "53") (name "Net-(IC1B-I1)") (class "Default")
      (node (ref "C-2") (pin "2") (pinfunction "2_2") (pintype "passive"))
      (node (ref "IC1") (pin "5") (pinfunction "I1_5") (pintype "input"))
    )
    (net (code "54") (name "Net-(IC1C-I1)") (class "Default")
      (node (ref "C-3") (pin "2") (pinfunction "2_2") (pintype "passive"))
      (node (ref "IC1") (pin "9") (pinfunction "I1_9") (pintype "input"))
    )
    (net (code "55") (name "Net-(IC1D-I1)") (class "Default")
      (node (ref "C2") (pin "2") (pinfunction "2_2") (pintype "passive"))
      (node (ref "IC1") (pin "12") (pinfunction "I1_12") (pintype "input"))
    )
    (net (code "56") (name "Net-(IC2A-I1)") (class "Default")
      (node (ref "C4") (pin "2") (pinfunction "2_2") (pintype "passive"))
      (node (ref "IC2") (pin "2") (pinfunction "I1_2") (pintype "input"))
    )
    (net (code "57") (name "Net-(IC2B-I1)") (class "Default")
      (node (ref "C3") (pin "2") (pinfunction "2_2") (pintype "passive"))
      (node (ref "IC2") (pin "5") (pinfunction "I1_5") (pintype "input"))
    )
    (net (code "58") (name "Net-(IC2C-I1)") (class "Default")
      (node (ref "C5") (pin "2") (pinfunction "2_2") (pintype "passive"))
      (node (ref "IC2") (pin "9") (pinfunction "I1_9") (pintype "input"))
    )
    (net (code "59") (name "Net-(IC2D-I1)") (class "Default")
      (node (ref "C6") (pin "2") (pinfunction "2_2") (pintype "passive"))
      (node (ref "IC2") (pin "12") (pinfunction "I1_12") (pintype "input"))
    )
    (net (code "60") (name "Net-(IC3A-I1)") (class "Default")
      (node (ref "C-10") (pin "2") (pinfunction "2_2") (pintype "passive"))
      (node (ref "IC3") (pin "2") (pinfunction "I1_2") (pintype "input"))
    )
    (net (code "61") (name "Net-(IC3B-I1)") (class "Default")
      (node (ref "C-11") (pin "2") (pinfunction "2_2") (pintype "passive"))
      (node (ref "IC3") (pin "5") (pinfunction "I1_5") (pintype "input"))
    )
    (net (code "62") (name "Net-(IC3C-I1)") (class "Default")
      (node (ref "C-12") (pin "2") (pinfunction "2_2") (pintype "passive"))
      (node (ref "IC3") (pin "9") (pinfunction "I1_9") (pintype "input"))
    )
    (net (code "63") (name "Net-(IC3D-I1)") (class "Default")
      (node (ref "C16") (pin "2") (pinfunction "2_2") (pintype "passive"))
      (node (ref "IC3") (pin "12") (pinfunction "I1_12") (pintype "input"))
    )
    (net (code "64") (name "Net-(IC4A-I1)") (class "Default")
      (node (ref "C1") (pin "2") (pinfunction "2_2") (pintype "passive"))
      (node (ref "IC4") (pin "2") (pinfunction "I1_2") (pintype "input"))
    )
    (net (code "65") (name "Net-(IC4B-I1)") (class "Default")
      (node (ref "C17") (pin "2") (pinfunction "2_2") (pintype "passive"))
      (node (ref "IC4") (pin "5") (pinfunction "I1_5") (pintype "input"))
    )
    (net (code "66") (name "Net-(IC4C-I1)") (class "Default")
      (node (ref "C9") (pin "2") (pinfunction "2_2") (pintype "passive"))
      (node (ref "IC4") (pin "9") (pinfunction "I1_9") (pintype "input"))
    )
    (net (code "67") (name "Net-(IC4D-I1)") (class "Default")
      (node (ref "C18") (pin "2") (pinfunction "2_2") (pintype "passive"))
      (node (ref "IC4") (pin "12") (pinfunction "I1_12") (pintype "input"))
    )
    (net (code "68") (name "Net-(IC12A-O)") (class "Default")
      (node (ref "IC12") (pin "12") (pinfunction "O_12") (pintype "output"))
      (node (ref "R19") (pin "1") (pinfunction "1_1") (pintype "passive"))
    )
    (net (code "69") (name "Net-(IC12C-I)") (class "Default")
      (node (ref "IC12") (pin "9") (pinfunction "I_9") (pintype "input"))
      (node (ref "R2") (pin "1") (pinfunction "1_1") (pintype "passive"))
      (node (ref "SRCLK1") (pin "3") (pinfunction "EMIT_3") (pintype "passive"))
    )
    (net (code "70") (name "Net-(IC12D-I)") (class "Default")
      (node (ref "IC12") (pin "1") (pinfunction "I_1") (pintype "input"))
      (node (ref "R25") (pin "1") (pinfunction "1_1") (pintype "passive"))
      (node (ref "S-OUT") (pin "3") (pinfunction "EMIT_3") (pintype "passive"))
    )
    (net (code "71") (name "Net-(IC12E-I)") (class "Default")
      (node (ref "IC12") (pin "3") (pinfunction "I_3") (pintype "input"))
      (node (ref "R1") (pin "1") (pinfunction "1_1") (pintype "passive"))
      (node (ref "RCLK1") (pin "3") (pinfunction "EMIT_3") (pintype "passive"))
    )
    (net (code "72") (name "Net-(IC14B-O)") (class "Default")
      (node (ref "IC14") (pin "6") (pinfunction "O_6") (pintype "tri_state"))
      (node (ref "R22") (pin "1") (pinfunction "1_1") (pintype "passive"))
    )
    (net (code "73") (name "Net-(IC14C-O)") (class "Default")
      (node (ref "IC14") (pin "8") (pinfunction "O_8") (pintype "tri_state"))
      (node (ref "R23") (pin "1") (pinfunction "1_1") (pintype "passive"))
    )
    (net (code "74") (name "Net-(IC14D-O)") (class "Default")
      (node (ref "IC14") (pin "11") (pinfunction "O_11") (pintype "tri_state"))
      (node (ref "R21") (pin "1") (pinfunction "1_1") (pintype "passive"))
    )
    (net (code "75") (name "Net-(IC15A-I1)") (class "Default")
      (node (ref "C34") (pin "2") (pinfunction "2_2") (pintype "passive"))
      (node (ref "IC15") (pin "2") (pinfunction "I1_2") (pintype "input"))
    )
    (net (code "76") (name "Net-(IC15A-O)") (class "Default")
      (node (ref "IC15") (pin "3") (pinfunction "O_3") (pintype "output"))
      (node (ref "RN2") (pin "2") (pinfunction "2_2") (pintype "passive"))
      (node (ref "XH") (pin "1") (pinfunction "A_1") (pintype "passive"))
    )
    (net (code "77") (name "Net-(IC15B-I1)") (class "Default")
      (node (ref "C33") (pin "2") (pinfunction "2_2") (pintype "passive"))
      (node (ref "IC15") (pin "5") (pinfunction "I1_5") (pintype "input"))
    )
    (net (code "78") (name "Net-(IC15B-O)") (class "Default")
      (node (ref "IC15") (pin "6") (pinfunction "O_6") (pintype "output"))
      (node (ref "RN2") (pin "3") (pinfunction "2_3") (pintype "passive"))
      (node (ref "YH") (pin "1") (pinfunction "A_1") (pintype "passive"))
    )
    (net (code "79") (name "Net-(IC15C-I1)") (class "Default")
      (node (ref "C32") (pin "2") (pinfunction "2_2") (pintype "passive"))
      (node (ref "IC15") (pin "9") (pinfunction "I1_9") (pintype "input"))
    )
    (net (code "80") (name "Net-(IC15C-O)") (class "Default")
      (node (ref "IC15") (pin "8") (pinfunction "O_8") (pintype "output"))
      (node (ref "RN2") (pin "4") (pinfunction "2_4") (pintype "passive"))
      (node (ref "ZH") (pin "1") (pinfunction "A_1") (pintype "passive"))
    )
    (net (code "81") (name "Net-(IC15D-I1)") (class "Default")
      (node (ref "C31") (pin "2") (pinfunction "2_2") (pintype "passive"))
      (node (ref "IC15") (pin "12") (pinfunction "I1_12") (pintype "input"))
    )
    (net (code "82") (name "Net-(LED1-C)") (class "Default")
      (node (ref "LED1") (pin "K") (pinfunction "C_K") (pintype "passive"))
      (node (ref "R13") (pin "2") (pinfunction "2_2") (pintype "passive"))
    )
    (net (code "83") (name "Net-(LED2-C)") (class "Default")
      (node (ref "LED2") (pin "K") (pinfunction "C_K") (pintype "passive"))
      (node (ref "R12") (pin "2") (pinfunction "2_2") (pintype "passive"))
    )
    (net (code "84") (name "Net-(RCLK1-C)") (class "Default")
      (node (ref "R23") (pin "2") (pinfunction "2_2") (pintype "passive"))
      (node (ref "RCLK1") (pin "2") (pinfunction "C_2") (pintype "passive"))
    )
    (net (code "85") (name "Net-(S-INPUT-C)") (class "Default")
      (node (ref "R19") (pin "2") (pinfunction "2_2") (pintype "passive"))
      (node (ref "S-INPUT") (pin "2") (pinfunction "C_2") (pintype "passive"))
    )
    (net (code "86") (name "Net-(S-OUT-C)") (class "Default")
      (node (ref "R22") (pin "2") (pinfunction "2_2") (pintype "passive"))
      (node (ref "S-OUT") (pin "2") (pinfunction "C_2") (pintype "passive"))
    )
    (net (code "87") (name "Net-(SRCLK1-C)") (class "Default")
      (node (ref "R21") (pin "2") (pinfunction "2_2") (pintype "passive"))
      (node (ref "SRCLK1") (pin "2") (pinfunction "C_2") (pintype "passive"))
    )
    (net (code "88") (name "O12") (class "Default")
      (node (ref "IC11") (pin "13") (pinfunction "A2_13") (pintype "input"))
      (node (ref "IC7") (pin "15") (pinfunction "QA_15") (pintype "tri_state"))
    )
    (net (code "89") (name "O13") (class "Default")
      (node (ref "IC11") (pin "11") (pinfunction "A1_11") (pintype "input"))
      (node (ref "IC7") (pin "1") (pinfunction "QB_1") (pintype "tri_state"))
    )
    (net (code "90") (name "O14") (class "Default")
      (node (ref "IC11") (pin "8") (pinfunction "A4_8") (pintype "input"))
      (node (ref "IC7") (pin "2") (pinfunction "QC_2") (pintype "tri_state"))
    )
    (net (code "91") (name "O15") (class "Default")
      (node (ref "IC11") (pin "6") (pinfunction "A3_6") (pintype "input"))
      (node (ref "IC7") (pin "3") (pinfunction "QD_3") (pintype "tri_state"))
    )
    (net (code "92") (name "O16") (class "Default")
      (node (ref "IC11") (pin "4") (pinfunction "A2_4") (pintype "input"))
      (node (ref "IC7") (pin "4") (pinfunction "QE_4") (pintype "tri_state"))
    )
    (net (code "93") (name "O17") (class "Default")
      (node (ref "IC11") (pin "2") (pinfunction "A1_2") (pintype "input"))
      (node (ref "IC7") (pin "5") (pinfunction "QF_5") (pintype "tri_state"))
    )
    (net (code "94") (name "O19") (class "Default")
      (node (ref "IC11") (pin "17") (pinfunction "A4_17") (pintype "input"))
      (node (ref "IC7") (pin "7") (pinfunction "QH_7") (pintype "tri_state"))
    )
    (net (code "95") (name "O22") (class "Default")
      (node (ref "IC10") (pin "13") (pinfunction "A2_13") (pintype "input"))
      (node (ref "IC8") (pin "15") (pinfunction "QA_15") (pintype "tri_state"))
    )
    (net (code "96") (name "O23") (class "Default")
      (node (ref "IC10") (pin "11") (pinfunction "A1_11") (pintype "input"))
      (node (ref "IC8") (pin "1") (pinfunction "QB_1") (pintype "tri_state"))
    )
    (net (code "97") (name "O24") (class "Default")
      (node (ref "IC10") (pin "8") (pinfunction "A4_8") (pintype "input"))
      (node (ref "IC8") (pin "2") (pinfunction "QC_2") (pintype "tri_state"))
    )
    (net (code "98") (name "O25") (class "Default")
      (node (ref "IC10") (pin "6") (pinfunction "A3_6") (pintype "input"))
      (node (ref "IC8") (pin "3") (pinfunction "QD_3") (pintype "tri_state"))
    )
    (net (code "99") (name "O26") (class "Default")
      (node (ref "IC10") (pin "4") (pinfunction "A2_4") (pintype "input"))
      (node (ref "IC8") (pin "4") (pinfunction "QE_4") (pintype "tri_state"))
    )
    (net (code "100") (name "O27") (class "Default")
      (node (ref "IC10") (pin "2") (pinfunction "A1_2") (pintype "input"))
      (node (ref "IC8") (pin "5") (pinfunction "QF_5") (pintype "tri_state"))
    )
    (net (code "101") (name "O28") (class "Default")
      (node (ref "IC10") (pin "15") (pinfunction "A3_15") (pintype "input"))
      (node (ref "IC8") (pin "6") (pinfunction "QG_6") (pintype "tri_state"))
    )
    (net (code "102") (name "O29") (class "Default")
      (node (ref "IC10") (pin "17") (pinfunction "A4_17") (pintype "input"))
      (node (ref "IC8") (pin "7") (pinfunction "QH_7") (pintype "tri_state"))
    )
    (net (code "103") (name "OP12") (class "Default")
      (node (ref "IC11") (pin "7") (pinfunction "Y2_7") (pintype "tri_state"))
      (node (ref "OUT1") (pin "2") (pinfunction "1_2") (pintype "passive"))
      (node (ref "OUTPUT1") (pin "2") (pinfunction "2_2") (pintype "passive"))
    )
    (net (code "104") (name "OP13") (class "Default")
      (node (ref "IC11") (pin "9") (pinfunction "Y1_9") (pintype "tri_state"))
      (node (ref "OUT1") (pin "3") (pinfunction "1_3") (pintype "passive"))
      (node (ref "OUTPUT1") (pin "3") (pinfunction "3_3") (pintype "passive"))
    )
    (net (code "105") (name "OP14") (class "Default")
      (node (ref "IC11") (pin "12") (pinfunction "Y4_12") (pintype "tri_state"))
      (node (ref "OUT1") (pin "4") (pinfunction "1_4") (pintype "passive"))
      (node (ref "OUTPUT1") (pin "4") (pinfunction "4_4") (pintype "passive"))
    )
    (net (code "106") (name "OP15") (class "Default")
      (node (ref "IC11") (pin "14") (pinfunction "Y3_14") (pintype "tri_state"))
      (node (ref "OUT1") (pin "5") (pinfunction "1_5") (pintype "passive"))
      (node (ref "OUTPUT1") (pin "5") (pinfunction "5_5") (pintype "passive"))
    )
    (net (code "107") (name "OP16") (class "Default")
      (node (ref "IC11") (pin "16") (pinfunction "Y2_16") (pintype "tri_state"))
      (node (ref "OUT1") (pin "6") (pinfunction "1_6") (pintype "passive"))
      (node (ref "OUTPUT1") (pin "6") (pinfunction "6_6") (pintype "passive"))
    )
    (net (code "108") (name "OP17") (class "Default")
      (node (ref "IC11") (pin "18") (pinfunction "Y1_18") (pintype "tri_state"))
      (node (ref "OUT1") (pin "7") (pinfunction "1_7") (pintype "passive"))
      (node (ref "OUTPUT1") (pin "7") (pinfunction "7_7") (pintype "passive"))
    )
    (net (code "109") (name "OP18") (class "Default")
      (node (ref "IC11") (pin "5") (pinfunction "Y3_5") (pintype "tri_state"))
      (node (ref "OUT1") (pin "8") (pinfunction "1_8") (pintype "passive"))
      (node (ref "OUTPUT1") (pin "8") (pinfunction "8_8") (pintype "passive"))
    )
    (net (code "110") (name "OP19") (class "Default")
      (node (ref "IC11") (pin "3") (pinfunction "Y4_3") (pintype "tri_state"))
      (node (ref "OUT1") (pin "9") (pinfunction "1_9") (pintype "passive"))
      (node (ref "OUTPUT1") (pin "9") (pinfunction "9_9") (pintype "passive"))
    )
    (net (code "111") (name "OP22") (class "Default")
      (node (ref "IC10") (pin "7") (pinfunction "Y2_7") (pintype "tri_state"))
      (node (ref "OUT2") (pin "2") (pinfunction "1_2") (pintype "passive"))
      (node (ref "OUTPUT2") (pin "2") (pinfunction "2_2") (pintype "passive"))
    )
    (net (code "112") (name "OP23") (class "Default")
      (node (ref "IC10") (pin "9") (pinfunction "Y1_9") (pintype "tri_state"))
      (node (ref "OUT2") (pin "3") (pinfunction "1_3") (pintype "passive"))
      (node (ref "OUTPUT2") (pin "3") (pinfunction "3_3") (pintype "passive"))
    )
    (net (code "113") (name "OP24") (class "Default")
      (node (ref "IC10") (pin "12") (pinfunction "Y4_12") (pintype "tri_state"))
      (node (ref "OUT2") (pin "4") (pinfunction "1_4") (pintype "passive"))
      (node (ref "OUTPUT2") (pin "4") (pinfunction "4_4") (pintype "passive"))
    )
    (net (code "114") (name "OP25") (class "Default")
      (node (ref "IC10") (pin "14") (pinfunction "Y3_14") (pintype "tri_state"))
      (node (ref "OUT2") (pin "5") (pinfunction "1_5") (pintype "passive"))
      (node (ref "OUTPUT2") (pin "5") (pinfunction "5_5") (pintype "passive"))
    )
    (net (code "115") (name "OP26") (class "Default")
      (node (ref "IC10") (pin "16") (pinfunction "Y2_16") (pintype "tri_state"))
      (node (ref "OUT2") (pin "6") (pinfunction "1_6") (pintype "passive"))
      (node (ref "OUTPUT2") (pin "6") (pinfunction "6_6") (pintype "passive"))
    )
    (net (code "116") (name "OP27") (class "Default")
      (node (ref "IC10") (pin "18") (pinfunction "Y1_18") (pintype "tri_state"))
      (node (ref "OUT2") (pin "7") (pinfunction "1_7") (pintype "passive"))
      (node (ref "OUTPUT2") (pin "7") (pinfunction "7_7") (pintype "passive"))
    )
    (net (code "117") (name "OP28") (class "Default")
      (node (ref "IC10") (pin "5") (pinfunction "Y3_5") (pintype "tri_state"))
      (node (ref "OUT2") (pin "8") (pinfunction "1_8") (pintype "passive"))
      (node (ref "OUTPUT2") (pin "8") (pinfunction "8_8") (pintype "passive"))
    )
    (net (code "118") (name "OP29") (class "Default")
      (node (ref "IC10") (pin "3") (pinfunction "Y4_3") (pintype "tri_state"))
      (node (ref "OUT2") (pin "9") (pinfunction "1_9") (pintype "passive"))
      (node (ref "OUTPUT2") (pin "9") (pinfunction "9_9") (pintype "passive"))
    )
    (net (code "119") (name "P1") (class "Default")
      (node (ref "DBM") (pin "1") (pinfunction "1_1") (pintype "passive"))
    )
    (net (code "120") (name "P2") (class "Default")
      (node (ref "DBM") (pin "2") (pinfunction "2_2") (pintype "passive"))
      (node (ref "IC13") (pin "1") (pinfunction "I1_1") (pintype "input"))
    )
    (net (code "121") (name "P3") (class "Default")
      (node (ref "DBM") (pin "3") (pinfunction "3_3") (pintype "passive"))
      (node (ref "IC13") (pin "2") (pinfunction "I2_2") (pintype "input"))
    )
    (net (code "122") (name "P4") (class "Default")
      (node (ref "DBM") (pin "4") (pinfunction "4_4") (pintype "passive"))
      (node (ref "IC13") (pin "3") (pinfunction "I3_3") (pintype "input"))
    )
    (net (code "123") (name "P5") (class "Default")
      (node (ref "DBM") (pin "5") (pinfunction "5_5") (pintype "passive"))
      (node (ref "IC13") (pin "4") (pinfunction "I4_4") (pintype "input"))
    )
    (net (code "124") (name "P6") (class "Default")
      (node (ref "DBM") (pin "6") (pinfunction "6_6") (pintype "passive"))
      (node (ref "IC13") (pin "5") (pinfunction "I5_5") (pintype "input"))
    )
    (net (code "125") (name "P7") (class "Default")
      (node (ref "DBM") (pin "7") (pinfunction "7_7") (pintype "passive"))
      (node (ref "IC13") (pin "6") (pinfunction "I6_6") (pintype "input"))
    )
    (net (code "126") (name "P8") (class "Default")
      (node (ref "DBM") (pin "8") (pinfunction "8_8") (pintype "passive"))
      (node (ref "IC13") (pin "7") (pinfunction "I7_7") (pintype "input"))
    )
    (net (code "127") (name "P9") (class "Default")
      (node (ref "DBM") (pin "9") (pinfunction "9_9") (pintype "passive"))
      (node (ref "IC13") (pin "8") (pinfunction "I8_8") (pintype "input"))
    )
    (net (code "128") (name "P10") (class "Default")
      (node (ref "DBM") (pin "10") (pinfunction "10_10") (pintype "passive"))
      (node (ref "RN3") (pin "2") (pinfunction "2_2") (pintype "passive"))
      (node (ref "XH") (pin "4") (pinfunction "COL_4") (pintype "passive"))
    )
    (net (code "129") (name "P11") (class "Default")
      (node (ref "DBM") (pin "11") (pinfunction "11_11") (pintype "passive"))
      (node (ref "RN3") (pin "3") (pinfunction "2_3") (pintype "passive"))
      (node (ref "YH") (pin "4") (pinfunction "COL_4") (pintype "passive"))
    )
    (net (code "130") (name "P12") (class "Default")
      (node (ref "DBM") (pin "12") (pinfunction "12_12") (pintype "passive"))
      (node (ref "RN3") (pin "4") (pinfunction "2_4") (pintype "passive"))
      (node (ref "ZH") (pin "4") (pinfunction "COL_4") (pintype "passive"))
    )
    (net (code "131") (name "P13") (class "Default")
      (node (ref "AH") (pin "4") (pinfunction "COL_4") (pintype "passive"))
      (node (ref "DBM") (pin "13") (pinfunction "13_13") (pintype "passive"))
      (node (ref "RN3") (pin "5") (pinfunction "2_5") (pintype "passive"))
    )
    (net (code "132") (name "P14") (class "Default")
      (node (ref "DBM") (pin "14") (pinfunction "14_14") (pintype "passive"))
      (node (ref "IC14") (pin "5") (pinfunction "I_5") (pintype "input"))
    )
    (net (code "133") (name "P15") (class "Default")
      (node (ref "DBM") (pin "15") (pinfunction "15_15") (pintype "passive"))
      (node (ref "R26") (pin "2") (pinfunction "2_2") (pintype "passive"))
      (node (ref "S-INPUT") (pin "4") (pinfunction "COL_4") (pintype "passive"))
    )
    (net (code "134") (name "P16") (class "Default")
      (node (ref "DBM") (pin "16") (pinfunction "16_16") (pintype "passive"))
      (node (ref "IC14") (pin "9") (pinfunction "I_9") (pintype "input"))
    )
    (net (code "135") (name "P17") (class "Default")
      (node (ref "DBM") (pin "17") (pinfunction "17_17") (pintype "passive"))
      (node (ref "IC14") (pin "12") (pinfunction "I_12") (pintype "input"))
    )
    (net (code "136") (name "PCGND") (class "Default")
      (node (ref "A") (pin "1") (pinfunction "S_1") (pintype "passive"))
      (node (ref "AH") (pin "3") (pinfunction "EMIT_3") (pintype "passive"))
      (node (ref "C28") (pin "1") (pinfunction "1_1") (pintype "passive"))
      (node (ref "C29") (pin "1") (pinfunction "1_1") (pintype "passive"))
      (node (ref "C30") (pin "-") (pinfunction "-_-") (pintype "passive"))
      (node (ref "DBM") (pin "18") (pinfunction "18_18") (pintype "passive"))
      (node (ref "DBM") (pin "19") (pinfunction "19_19") (pintype "passive"))
      (node (ref "DBM") (pin "20") (pinfunction "20_20") (pintype "passive"))
      (node (ref "DBM") (pin "21") (pinfunction "21_21") (pintype "passive"))
      (node (ref "DBM") (pin "22") (pinfunction "22_22") (pintype "passive"))
      (node (ref "DBM") (pin "23") (pinfunction "23_23") (pintype "passive"))
      (node (ref "DBM") (pin "24") (pinfunction "24_24") (pintype "passive"))
      (node (ref "DBM") (pin "25") (pinfunction "25_25") (pintype "passive"))
      (node (ref "DC1") (pin "3") (pinfunction "-VOUT_3") (pintype "passive"))
      (node (ref "IC13") (pin "9") (pinfunction "GND_9") (pintype "power_in"))
      (node (ref "IC14") (pin "10") (pinfunction "OE_10") (pintype "input"))
      (node (ref "IC14") (pin "13") (pinfunction "OE_13") (pintype "input"))
      (node (ref "IC14") (pin "2") (pinfunction "I_2") (pintype "input"))
      (node (ref "IC14") (pin "4") (pinfunction "OE_4") (pintype "input"))
      (node (ref "IC14") (pin "7") (pinfunction "GND_7") (pintype "power_in"))
      (node (ref "R12") (pin "1") (pinfunction "1_1") (pintype "passive"))
      (node (ref "S-INPUT") (pin "3") (pinfunction "EMIT_3") (pintype "passive"))
      (node (ref "X") (pin "1") (pinfunction "S_1") (pintype "passive"))
      (node (ref "XH") (pin "3") (pinfunction "EMIT_3") (pintype "passive"))
      (node (ref "Y") (pin "1") (pinfunction "S_1") (pintype "passive"))
      (node (ref "YH") (pin "3") (pinfunction "EMIT_3") (pintype "passive"))
      (node (ref "Z") (pin "1") (pinfunction "S_1") (pintype "passive"))
      (node (ref "ZH") (pin "3") (pinfunction "EMIT_3") (pintype "passive"))
    )
    (net (code "137") (name "PCV5") (class "Default")
      (node (ref "A") (pin "4") (pinfunction "S_4") (pintype "passive"))
      (node (ref "C28") (pin "2") (pinfunction "2_2") (pintype "passive"))
      (node (ref "C29") (pin "2") (pinfunction "2_2") (pintype "passive"))
      (node (ref "C30") (pin "+") (pinfunction "+_+") (pintype "passive"))
      (node (ref "DC1") (pin "4") (pinfunction "+VOUT_4") (pintype "passive"))
      (node (ref "IC13") (pin "10") (pinfunction "CD+_10") (pintype "passive"))
      (node (ref "LED2") (pin "A") (pinfunction "A_A") (pintype "passive"))
      (node (ref "RN3") (pin "1") (pinfunction "1_1") (pintype "passive"))
      (node (ref "X") (pin "4") (pinfunction "S_4") (pintype "passive"))
      (node (ref "Y") (pin "4") (pinfunction "S_4") (pintype "passive"))
      (node (ref "Z") (pin "4") (pinfunction "S_4") (pintype "passive"))
    )
    (net (code "138") (name "RCLK") (class "Default")
      (node (ref "IC12") (pin "11") (pinfunction "I_11") (pintype "input"))
      (node (ref "IC12") (pin "8") (pinfunction "O_8") (pintype "output"))
      (node (ref "IC5") (pin "12") (pinfunction "RCK_12") (pintype "input"))
      (node (ref "IC6") (pin "12") (pinfunction "RCK_12") (pintype "input"))
      (node (ref "IC7") (pin "12") (pinfunction "RCK_12") (pintype "input"))
      (node (ref "IC8") (pin "12") (pinfunction "RCK_12") (pintype "input"))
    )
    (net (code "139") (name "SPLY") (class "Default")
      (node (ref "RN5") (pin "1") (pinfunction "1_1") (pintype "passive"))
    )
    (net (code "140") (name "SRCLK") (class "Default")
      (node (ref "IC12") (pin "4") (pinfunction "O_4") (pintype "output"))
      (node (ref "IC5") (pin "11") (pinfunction "SRCK_11") (pintype "input"))
      (node (ref "IC6") (pin "11") (pinfunction "SRCK_11") (pintype "input"))
      (node (ref "IC7") (pin "11") (pinfunction "SCK_11") (pintype "input"))
      (node (ref "IC8") (pin "11") (pinfunction "SCK_11") (pintype "input"))
    )
    (net (code "141") (name "SRLD") (class "Default")
      (node (ref "IC12") (pin "10") (pinfunction "O_10") (pintype "output"))
      (node (ref "IC5") (pin "13") (pinfunction "SLD_13") (pintype "input"))
      (node (ref "IC6") (pin "13") (pinfunction "SLD_13") (pintype "input"))
    )
    (net (code "142") (name "V5") (class "Default")
      (node (ref ".") (pin "2") (pinfunction "KL_2") (pintype "passive"))
      (node (ref "C10") (pin "2") (pinfunction "2_2") (pintype "passive"))
      (node (ref "C11") (pin "2") (pinfunction "2_2") (pintype "passive"))
      (node (ref "C12") (pin "2") (pinfunction "2_2") (pintype "passive"))
      (node (ref "C13") (pin "2") (pinfunction "2_2") (pintype "passive"))
      (node (ref "C14") (pin "2") (pinfunction "2_2") (pintype "passive"))
      (node (ref "C15") (pin "2") (pinfunction "2_2") (pintype "passive"))
      (node (ref "C19") (pin "2") (pinfunction "2_2") (pintype "passive"))
      (node (ref "C20") (pin "2") (pinfunction "2_2") (pintype "passive"))
      (node (ref "C21") (pin "2") (pinfunction "2_2") (pintype "passive"))
      (node (ref "C22") (pin "2") (pinfunction "2_2") (pintype "passive"))
      (node (ref "C23") (pin "2") (pinfunction "2_2") (pintype "passive"))
      (node (ref "C24") (pin "2") (pinfunction "2_2") (pintype "passive"))
      (node (ref "C25") (pin "2") (pinfunction "2_2") (pintype "passive"))
      (node (ref "C26") (pin "2") (pinfunction "2_2") (pintype "passive"))
      (node (ref "C27") (pin "2") (pinfunction "2_2") (pintype "passive"))
      (node (ref "C35") (pin "2") (pinfunction "2_2") (pintype "passive"))
      (node (ref "C36") (pin "2") (pinfunction "2_2") (pintype "passive"))
      (node (ref "C37") (pin "2") (pinfunction "2_2") (pintype "passive"))
      (node (ref "C7") (pin "+") (pinfunction "+_+") (pintype "passive"))
      (node (ref "C8") (pin "2") (pinfunction "2_2") (pintype "passive"))
      (node (ref "DC1") (pin "2") (pinfunction "+VIN_2") (pintype "passive"))
      (node (ref "FIN") (pin "6") (pinfunction "1_6") (pintype "passive"))
      (node (ref "IC1") (pin "14") (pinfunction "VCC_14") (pintype "power_in"))
      (node (ref "IC10") (pin "20") (pinfunction "VCC_20") (pintype "power_in"))
      (node (ref "IC11") (pin "20") (pinfunction "VCC_20") (pintype "power_in"))
      (node (ref "IC12") (pin "14") (pinfunction "VCC_14") (pintype "power_in"))
      (node (ref "IC15") (pin "14") (pinfunction "VCC_14") (pintype "power_in"))
      (node (ref "IC2") (pin "14") (pinfunction "VCC_14") (pintype "power_in"))
      (node (ref "IC3") (pin "14") (pinfunction "VCC_14") (pintype "power_in"))
      (node (ref "IC4") (pin "14") (pinfunction "VCC_14") (pintype "power_in"))
      (node (ref "IC5") (pin "10") (pinfunction "SCL_10") (pintype "input"))
      (node (ref "IC5") (pin "16") (pinfunction "VCC_16") (pintype "power_in"))
      (node (ref "IC6") (pin "10") (pinfunction "SCL_10") (pintype "input"))
      (node (ref "IC6") (pin "16") (pinfunction "VCC_16") (pintype "power_in"))
      (node (ref "IC7") (pin "10") (pinfunction "SCL_10") (pintype "input"))
      (node (ref "IC7") (pin "16") (pinfunction "VCC_16") (pintype "power_in"))
      (node (ref "IC8") (pin "10") (pinfunction "SCL_10") (pintype "input"))
      (node (ref "IC8") (pin "16") (pinfunction "VCC_16") (pintype "power_in"))
      (node (ref "INPUT1") (pin "10") (pinfunction "10_10") (pintype "passive"))
      (node (ref "INPUT2") (pin "10") (pinfunction "10_10") (pintype "passive"))
      (node (ref "LED1") (pin "A") (pinfunction "A_A") (pintype "passive"))
      (node (ref "OUTPUT1") (pin "10") (pinfunction "10_10") (pintype "passive"))
      (node (ref "OUTPUT2") (pin "10") (pinfunction "10_10") (pintype "passive"))
      (node (ref "RCLK1") (pin "4") (pinfunction "COL_4") (pintype "passive"))
      (node (ref "RN1") (pin "1") (pinfunction "1_1") (pintype "passive"))
      (node (ref "RN2") (pin "1") (pinfunction "1_1") (pintype "passive"))
      (node (ref "RN4") (pin "1") (pinfunction "1_1") (pintype "passive"))
      (node (ref "S-INPUT") (pin "1") (pinfunction "A_1") (pintype "passive"))
      (node (ref "S-OUT") (pin "4") (pinfunction "COL_4") (pintype "passive"))
      (node (ref "SRCLK1") (pin "4") (pinfunction "COL_4") (pintype "passive"))
    )
    (net (code "143") (name "V5PC") (class "Default")
      (node (ref "IC14") (pin "1") (pinfunction "OE_1") (pintype "input"))
      (node (ref "IC14") (pin "14") (pinfunction "VCC_14") (pintype "power_in"))
      (node (ref "R26") (pin "1") (pinfunction "1_1") (pintype "passive"))
      (node (ref "RCLK1") (pin "1") (pinfunction "A_1") (pintype "passive"))
      (node (ref "S-OUT") (pin "1") (pinfunction "A_1") (pintype "passive"))
      (node (ref "SRCLK1") (pin "1") (pinfunction "A_1") (pintype "passive"))
    )
    (net (code "144") (name "unconnected-(IC5A-SER-Pad14)") (class "Default")
      (node (ref "IC5") (pin "14") (pinfunction "SER_14") (pintype "input"))
    )
    (net (code "145") (name "unconnected-(IC8A-QH*-Pad9)") (class "Default")
      (node (ref "IC8") (pin "9") (pinfunction "QH*_9") (pintype "tri_state"))
    )
    (net (code "146") (name "unconnected-(IC14A-O-Pad3)") (class "Default")
      (node (ref "IC14") (pin "3") (pinfunction "O_3") (pintype "tri_state"))
    )
  )
)
